# xbee-door-alert.net
KiCad netlist of a schematic drawn in EAGLE
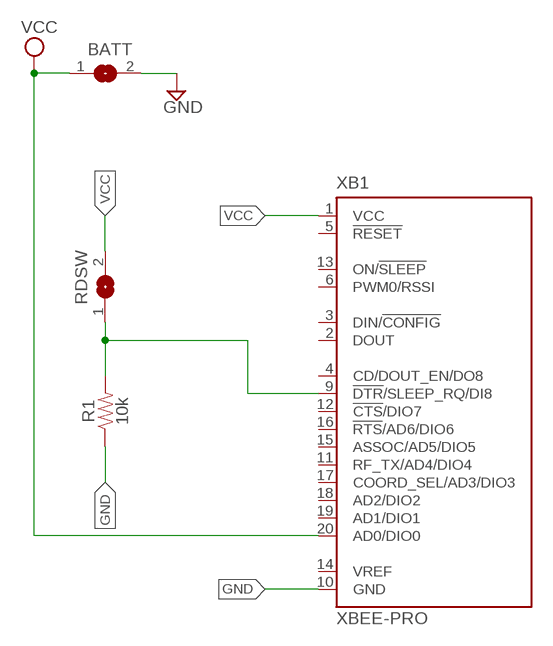
[diagram p0: schematic, sheet 1]

(export (version "E")
  (design (tool "Eeschema 10.0.6"))
  (components
    (comp (ref "BATT")
      (value "SJW")
      (footprint "eagle-import:SJW")
      (libsource (lib "eagle-import") (part "SJW"))
    )
    (comp (ref "R1")
      (value "10k")
      (footprint "eagle-import:AXIAL-0.3")
      (libsource (lib "eagle-import") (part "10KOHM-HORIZ-1/4W-5%"))
    )
    (comp (ref "RDSW")
      (value "SJW")
      (footprint "eagle-import:SJW")
      (libsource (lib "eagle-import") (part "SJW"))
    )
    (comp (ref "XB1")
      (value "XBEE-PRO")
      (footprint "eagle-import:XBEE-PRO")
      (fields (field (name "MPN") "XBP24-AWI-001"))
      (libsource (lib "eagle-import") (part "XBEE-PRO"))
    )
  )
  (nets
    (net (code "1") (name "GND") (class "Default")
      (node (ref "BATT") (pin "2") (pinfunction "2_2") (pintype "passive"))
      (node (ref "R1") (pin "P$1") (pinfunction "1_P$1") (pintype "passive"))
      (node (ref "XB1") (pin "10") (pinfunction "GND_10") (pintype "power_in"))
    )
    (net (code "2") (name "Net-(R1-2)") (class "Default")
      (node (ref "R1") (pin "P$2") (pinfunction "2_P$2") (pintype "passive"))
      (node (ref "RDSW") (pin "1") (pinfunction "1_1") (pintype "passive"))
      (node (ref "XB1") (pin "9") (pinfunction "~{DTR}/SLEEP_RQ/DI8_9") (pintype "bidirectional"))
    )
    (net (code "3") (name "VCC") (class "Default")
      (node (ref "BATT") (pin "1") (pinfunction "1_1") (pintype "passive"))
      (node (ref "RDSW") (pin "2") (pinfunction "2_2") (pintype "passive"))
      (node (ref "XB1") (pin "1") (pinfunction "VCC_1") (pintype "power_in"))
      (node (ref "XB1") (pin "20") (pinfunction "AD0/DIO0_20") (pintype "bidirectional"))
    )
    (net (code "4") (name "unconnected-(XB1-AD1{slash}DIO1-Pad19)") (class "Default")
      (node (ref "XB1") (pin "19") (pinfunction "AD1/DIO1_19") (pintype "bidirectional"))
    )
    (net (code "5") (name "unconnected-(XB1-AD2{slash}DIO2-Pad18)") (class "Default")
      (node (ref "XB1") (pin "18") (pinfunction "AD2/DIO2_18") (pintype "bidirectional"))
    )
    (net (code "6") (name "unconnected-(XB1-ASSOC{slash}AD5{slash}DIO5-Pad15)") (class "Default")
      (node (ref "XB1") (pin "15") (pinfunction "ASSOC/AD5/DIO5_15") (pintype "bidirectional"))
    )
    (net (code "7") (name "unconnected-(XB1-CD{slash}DOUT_EN{slash}DO8-Pad4)") (class "Default")
      (node (ref "XB1") (pin "4") (pinfunction "CD/DOUT_EN/DO8_4") (pintype "output"))
    )
    (net (code "8") (name "unconnected-(XB1-COORD_SEL{slash}AD3{slash}DIO3-Pad17)") (class "Default")
      (node (ref "XB1") (pin "17") (pinfunction "COORD_SEL/AD3/DIO3_17") (pintype "bidirectional"))
    )
    (net (code "9") (name "unconnected-(XB1-DIN{slash}~{CONFIG}-Pad3)") (class "Default")
      (node (ref "XB1") (pin "3") (pinfunction "DIN/~{CONFIG}_3") (pintype "input"))
    )
    (net (code "10") (name "unconnected-(XB1-DOUT-Pad2)") (class "Default")
      (node (ref "XB1") (pin "2") (pinfunction "DOUT_2") (pintype "output"))
    )
    (net (code "11") (name "unconnected-(XB1-ON{slash}~{SLEEP}-Pad13)") (class "Default")
      (node (ref "XB1") (pin "13") (pinfunction "ON/~{SLEEP}_13") (pintype "output"))
    )
    (net (code "12") (name "unconnected-(XB1-PWM0{slash}RSSI-Pad6)") (class "Default")
      (node (ref "XB1") (pin "6") (pinfunction "PWM0/RSSI_6") (pintype "output"))
    )
    (net (code "13") (name "unconnected-(XB1-RF_TX{slash}AD4{slash}DIO4-Pad11)") (class "Default")
      (node (ref "XB1") (pin "11") (pinfunction "RF_TX/AD4/DIO4_11") (pintype "bidirectional"))
    )
    (net (code "14") (name "unconnected-(XB1-VREF-Pad14)") (class "Default")
      (node (ref "XB1") (pin "14") (pinfunction "VREF_14") (pintype "input"))
    )
    (net (code "15") (name "unconnected-(XB1-~{CTS}{slash}DIO7-Pad12)") (class "Default")
      (node (ref "XB1") (pin "12") (pinfunction "~{CTS}/DIO7_12") (pintype "bidirectional"))
    )
    (net (code "16") (name "unconnected-(XB1-~{RESET}-Pad5)") (class "Default")
      (node (ref "XB1") (pin "5") (pinfunction "~{RESET}_5") (pintype "input"))
    )
    (net (code "17") (name "unconnected-(XB1-~{RTS}{slash}AD6{slash}DIO6-Pad16)") (class "Default")
      (node (ref "XB1") (pin "16") (pinfunction "~{RTS}/AD6/DIO6_16") (pintype "bidirectional"))
    )
  )
)
